# CAN_QSPI.net
KiCad netlist of a schematic drawn in Altium Designer
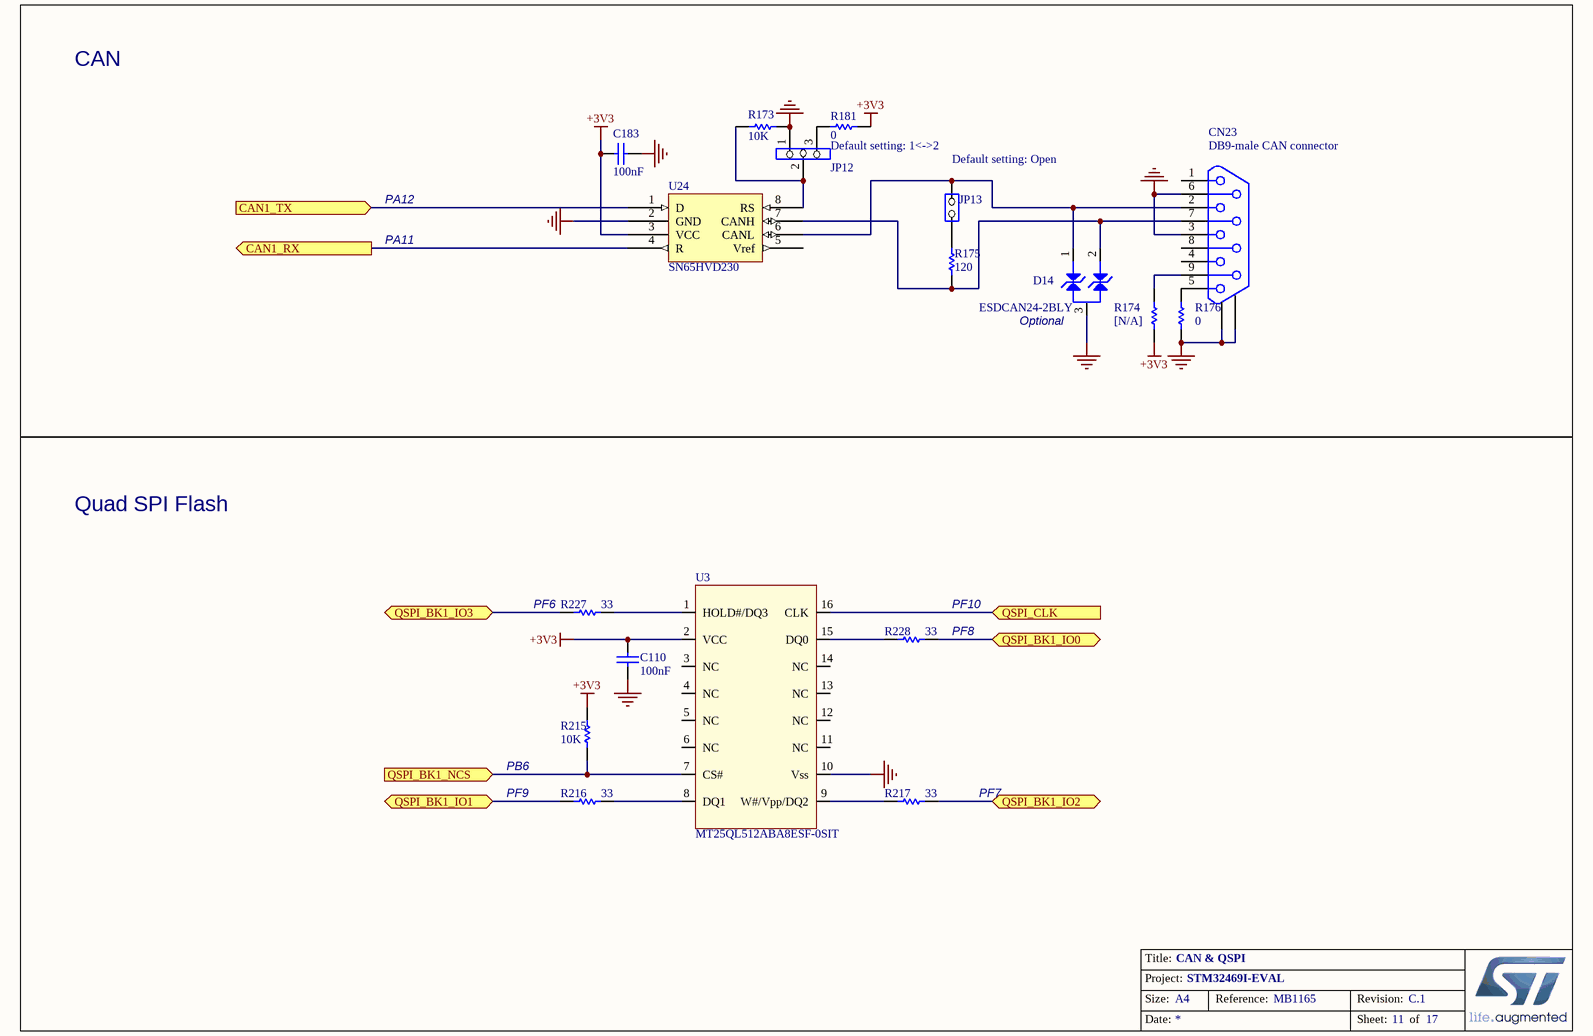
[diagram p0: CAN&QSPI.SchDoc]

(export (version "E")
  (design (tool "Eeschema 10.0.6"))
  (components
    (comp (ref "C110")
      (value "100nF")
      (footprint "0402C")
      (description "Capacitor")
      (fields (field (name "PUBLISHER") "Altium Limited"))
      (libsource (lib "Miscellaneous Devices") (part "Cap"))
    )
    (comp (ref "C183")
      (value "100nF")
      (footprint "0603C")
      (description "Capacitor")
      (fields (field (name "PUBLISHER") "Altium Limited"))
      (libsource (lib "Miscellaneous Devices") (part "Cap"))
    )
    (comp (ref "CN23")
      (value "DB9-male CAN connector")
      (footprint "DB9/M")
      (libsource (lib "mb1045") (part "DB9-CAN"))
    )
    (comp (ref "D14")
      (value "ESDCAN24-2BLY")
      (footprint "SOT-23")
      (libsource (lib "mb1045") (part "ESDCAN24-2BLY"))
    )
    (comp (ref "JP12") (value "~") (footprint "SIP3") (libsource (lib "STR910_SCHLIB") (part "Jumper3")))
    (comp (ref "JP13") (value "~") (footprint "SIP2") (libsource (lib "*") (part "JP2")))
    (comp (ref "R173")
      (value "10K")
      (footprint "0603R")
      (description "Resistor")
      (fields (field (name "PUBLISHER") "Altium Limited"))
      (libsource (lib "Miscellaneous Devices") (part "Res1"))
    )
    (comp (ref "R174")
      (value "[N/A]")
      (footprint "0603R")
      (description "Resistor")
      (fields (field (name "PUBLISHER") "Altium Limited"))
      (libsource (lib "Miscellaneous Devices") (part "res1"))
    )
    (comp (ref "R175")
      (value "120")
      (footprint "0603R")
      (description "Resistor")
      (fields (field (name "PUBLISHER") "Altium Limited"))
      (libsource (lib "Miscellaneous Devices") (part "res1"))
    )
    (comp (ref "R176")
      (value "0")
      (footprint "0603R")
      (description "Resistor")
      (fields (field (name "PUBLISHER") "Altium Limited"))
      (libsource (lib "Miscellaneous Devices") (part "res1"))
    )
    (comp (ref "R181")
      (value "0")
      (footprint "0603R")
      (description "Resistor")
      (fields (field (name "PUBLISHER") "Altium Limited"))
      (libsource (lib "Miscellaneous Devices") (part "res1"))
    )
    (comp (ref "R215")
      (value "10K")
      (footprint "0402R")
      (description "Resistor")
      (fields (field (name "PUBLISHER") "Altium Limited"))
      (libsource (lib "Miscellaneous Devices") (part "res1"))
    )
    (comp (ref "R216")
      (value "33")
      (footprint "0603R")
      (description "Resistor")
      (fields (field (name "PUBLISHER") "Altium Limited"))
      (libsource (lib "Miscellaneous Devices") (part "Res1"))
    )
    (comp (ref "R217")
      (value "33")
      (footprint "0603R")
      (description "Resistor")
      (fields (field (name "PUBLISHER") "Altium Limited"))
      (libsource (lib "Miscellaneous Devices") (part "Res1"))
    )
    (comp (ref "R227")
      (value "33")
      (footprint "0603R")
      (description "Resistor")
      (fields (field (name "PUBLISHER") "Altium Limited"))
      (libsource (lib "Miscellaneous Devices") (part "Res1"))
    )
    (comp (ref "R228")
      (value "33")
      (footprint "0603R")
      (description "Resistor")
      (fields (field (name "PUBLISHER") "Altium Limited"))
      (libsource (lib "Miscellaneous Devices") (part "Res1"))
    )
    (comp (ref "U3")
      (value "MT25QL512ABA8ESF-0SIT")
      (footprint "SOIC16W_1R27_10R3X10R33")
      (libsource (lib "MB1167") (part "QSPI_16pins"))
    )
    (comp (ref "U24")
      (value "SN65HVD230")
      (footprint "SOIC8_1R27_4R9X6")
      (libsource (lib "STR910_SCHLIB") (part "SN65HVD230D"))
    )
  )
  (nets
    (net (code "1") (name "+3V3") (class "Default")
      (node (ref "C110") (pin "1") (pinfunction "1_1") (pintype "passive"))
      (node (ref "C183") (pin "1") (pinfunction "1_1") (pintype "passive"))
      (node (ref "R174") (pin "1") (pinfunction "1_1") (pintype "passive"))
      (node (ref "R181") (pin "2") (pinfunction "2_2") (pintype "passive"))
      (node (ref "R215") (pin "1") (pinfunction "1_1") (pintype "passive"))
      (node (ref "U24") (pin "3") (pinfunction "VCC_3") (pintype "power_in"))
      (node (ref "U3") (pin "2") (pinfunction "VCC_2") (pintype "passive"))
    )
    (net (code "2") (name "/CAN1_RX") (class "Default")
      (node (ref "U24") (pin "4") (pinfunction "R_4") (pintype "output"))
    )
    (net (code "3") (name "/CAN1_TX") (class "Default")
      (node (ref "U24") (pin "1") (pinfunction "D_1") (pintype "input"))
    )
    (net (code "4") (name "/QSPI_BK1_IO0") (class "Default")
      (node (ref "R228") (pin "1") (pinfunction "1_1") (pintype "passive"))
    )
    (net (code "5") (name "/QSPI_BK1_IO1") (class "Default")
      (node (ref "R216") (pin "2") (pinfunction "2_2") (pintype "passive"))
    )
    (net (code "6") (name "/QSPI_BK1_IO2") (class "Default")
      (node (ref "R217") (pin "1") (pinfunction "1_1") (pintype "passive"))
    )
    (net (code "7") (name "/QSPI_BK1_IO3") (class "Default")
      (node (ref "R227") (pin "2") (pinfunction "2_2") (pintype "passive"))
    )
    (net (code "8") (name "/QSPI_BK1_NCS") (class "Default")
      (node (ref "R215") (pin "2") (pinfunction "2_2") (pintype "passive"))
      (node (ref "U3") (pin "7") (pinfunction "CS#_7") (pintype "passive"))
    )
    (net (code "9") (name "/QSPI_CLK") (class "Default")
      (node (ref "U3") (pin "16") (pinfunction "CLK_16") (pintype "passive"))
    )
    (net (code "10") (name "GND") (class "Default")
      (node (ref "C110") (pin "2") (pinfunction "2_2") (pintype "passive"))
      (node (ref "C183") (pin "2") (pinfunction "2_2") (pintype "passive"))
      (node (ref "CN23") (pin "10") (pinfunction "10_10") (pintype "passive"))
      (node (ref "CN23") (pin "11") (pinfunction "11_11") (pintype "passive"))
      (node (ref "CN23") (pin "3") (pinfunction "3_3") (pintype "passive"))
      (node (ref "CN23") (pin "6") (pinfunction "6_6") (pintype "passive"))
      (node (ref "D14") (pin "3") (pinfunction "3_3") (pintype "passive"))
      (node (ref "JP12") (pin "1") (pintype "passive"))
      (node (ref "R173") (pin "2") (pinfunction "2_2") (pintype "passive"))
      (node (ref "R176") (pin "1") (pinfunction "1_1") (pintype "passive"))
      (node (ref "U24") (pin "2") (pinfunction "GND_2") (pintype "power_in"))
      (node (ref "U3") (pin "10") (pinfunction "Vss_10") (pintype "passive"))
    )
    (net (code "11") (name "Net-(CN23-Pad5)") (class "Default")
      (node (ref "CN23") (pin "5") (pinfunction "5_5") (pintype "passive"))
      (node (ref "R176") (pin "2") (pinfunction "2_2") (pintype "passive"))
    )
    (net (code "12") (name "Net-(CN23-Pad9)") (class "Default")
      (node (ref "CN23") (pin "9") (pinfunction "9_9") (pintype "passive"))
      (node (ref "R174") (pin "2") (pinfunction "2_2") (pintype "passive"))
    )
    (net (code "13") (name "Net-(JP12-Pad3)") (class "Default")
      (node (ref "JP12") (pin "3") (pintype "passive"))
      (node (ref "R181") (pin "1") (pinfunction "1_1") (pintype "passive"))
    )
    (net (code "14") (name "Net-(JP13-COMMON)") (class "Default")
      (node (ref "JP13") (pin "1") (pinfunction "COMMON_1") (pintype "passive"))
      (node (ref "R175") (pin "2") (pinfunction "2_2") (pintype "passive"))
    )
    (net (code "15") (name "Net-(JP13-NO)") (class "Default")
      (node (ref "CN23") (pin "2") (pinfunction "2_2") (pintype "passive"))
      (node (ref "D14") (pin "1") (pinfunction "1_1") (pintype "passive"))
      (node (ref "JP13") (pin "2") (pinfunction "NO_2") (pintype "passive"))
      (node (ref "U24") (pin "6") (pinfunction "CANL_6") (pintype "bidirectional"))
    )
    (net (code "16") (name "Net-(U3-DQ0)") (class "Default")
      (node (ref "R228") (pin "2") (pinfunction "2_2") (pintype "passive"))
      (node (ref "U3") (pin "15") (pinfunction "DQ0_15") (pintype "passive"))
    )
    (net (code "17") (name "Net-(U3-DQ1)") (class "Default")
      (node (ref "R216") (pin "1") (pinfunction "1_1") (pintype "passive"))
      (node (ref "U3") (pin "8") (pinfunction "DQ1_8") (pintype "passive"))
    )
    (net (code "18") (name "Net-(U3-HOLD#{slash}DQ3)") (class "Default")
      (node (ref "R227") (pin "1") (pinfunction "1_1") (pintype "passive"))
      (node (ref "U3") (pin "1") (pinfunction "HOLD#/DQ3_1") (pintype "passive"))
    )
    (net (code "19") (name "Net-(U3-W#{slash}Vpp{slash}DQ2)") (class "Default")
      (node (ref "R217") (pin "2") (pinfunction "2_2") (pintype "passive"))
      (node (ref "U3") (pin "9") (pinfunction "W#/Vpp/DQ2_9") (pintype "passive"))
    )
    (net (code "20") (name "Net-(U24-CANH)") (class "Default")
      (node (ref "CN23") (pin "7") (pinfunction "7_7") (pintype "passive"))
      (node (ref "D14") (pin "2") (pinfunction "2_2") (pintype "passive"))
      (node (ref "R175") (pin "1") (pinfunction "1_1") (pintype "passive"))
      (node (ref "U24") (pin "7") (pinfunction "CANH_7") (pintype "bidirectional"))
    )
    (net (code "21") (name "Net-(U24-RS)") (class "Default")
      (node (ref "JP12") (pin "2") (pintype "passive"))
      (node (ref "R173") (pin "1") (pinfunction "1_1") (pintype "passive"))
      (node (ref "U24") (pin "8") (pinfunction "RS_8") (pintype "input"))
    )
    (net (code "22") (name "unconnected-(CN23-Pad1)") (class "Default")
      (node (ref "CN23") (pin "1") (pinfunction "1_1") (pintype "passive"))
    )
    (net (code "23") (name "unconnected-(CN23-Pad4)") (class "Default")
      (node (ref "CN23") (pin "4") (pinfunction "4_4") (pintype "passive"))
    )
    (net (code "24") (name "unconnected-(CN23-Pad8)") (class "Default")
      (node (ref "CN23") (pin "8") (pinfunction "8_8") (pintype "passive"))
    )
    (net (code "25") (name "unconnected-(U3-NC-Pad3)") (class "Default")
      (node (ref "U3") (pin "3") (pinfunction "NC_3") (pintype "passive"))
    )
    (net (code "26") (name "unconnected-(U3-NC-Pad4)") (class "Default")
      (node (ref "U3") (pin "4") (pinfunction "NC_4") (pintype "passive"))
    )
    (net (code "27") (name "unconnected-(U3-NC-Pad5)") (class "Default")
      (node (ref "U3") (pin "5") (pinfunction "NC_5") (pintype "passive"))
    )
    (net (code "28") (name "unconnected-(U3-NC-Pad6)") (class "Default")
      (node (ref "U3") (pin "6") (pinfunction "NC_6") (pintype "passive"))
    )
    (net (code "29") (name "unconnected-(U3-NC-Pad11)") (class "Default")
      (node (ref "U3") (pin "11") (pinfunction "NC_11") (pintype "passive"))
    )
    (net (code "30") (name "unconnected-(U3-NC-Pad12)") (class "Default")
      (node (ref "U3") (pin "12") (pinfunction "NC_12") (pintype "passive"))
    )
    (net (code "31") (name "unconnected-(U3-NC-Pad13)") (class "Default")
      (node (ref "U3") (pin "13") (pinfunction "NC_13") (pintype "passive"))
    )
    (net (code "32") (name "unconnected-(U3-NC-Pad14)") (class "Default")
      (node (ref "U3") (pin "14") (pinfunction "NC_14") (pintype "passive"))
    )
    (net (code "33") (name "unconnected-(U24-Vref-Pad5)") (class "Default")
      (node (ref "U24") (pin "5") (pinfunction "Vref_5") (pintype "output"))
    )
  )
)
